# dcf77_clock.net
KiCad netlist of a schematic drawn in EAGLE
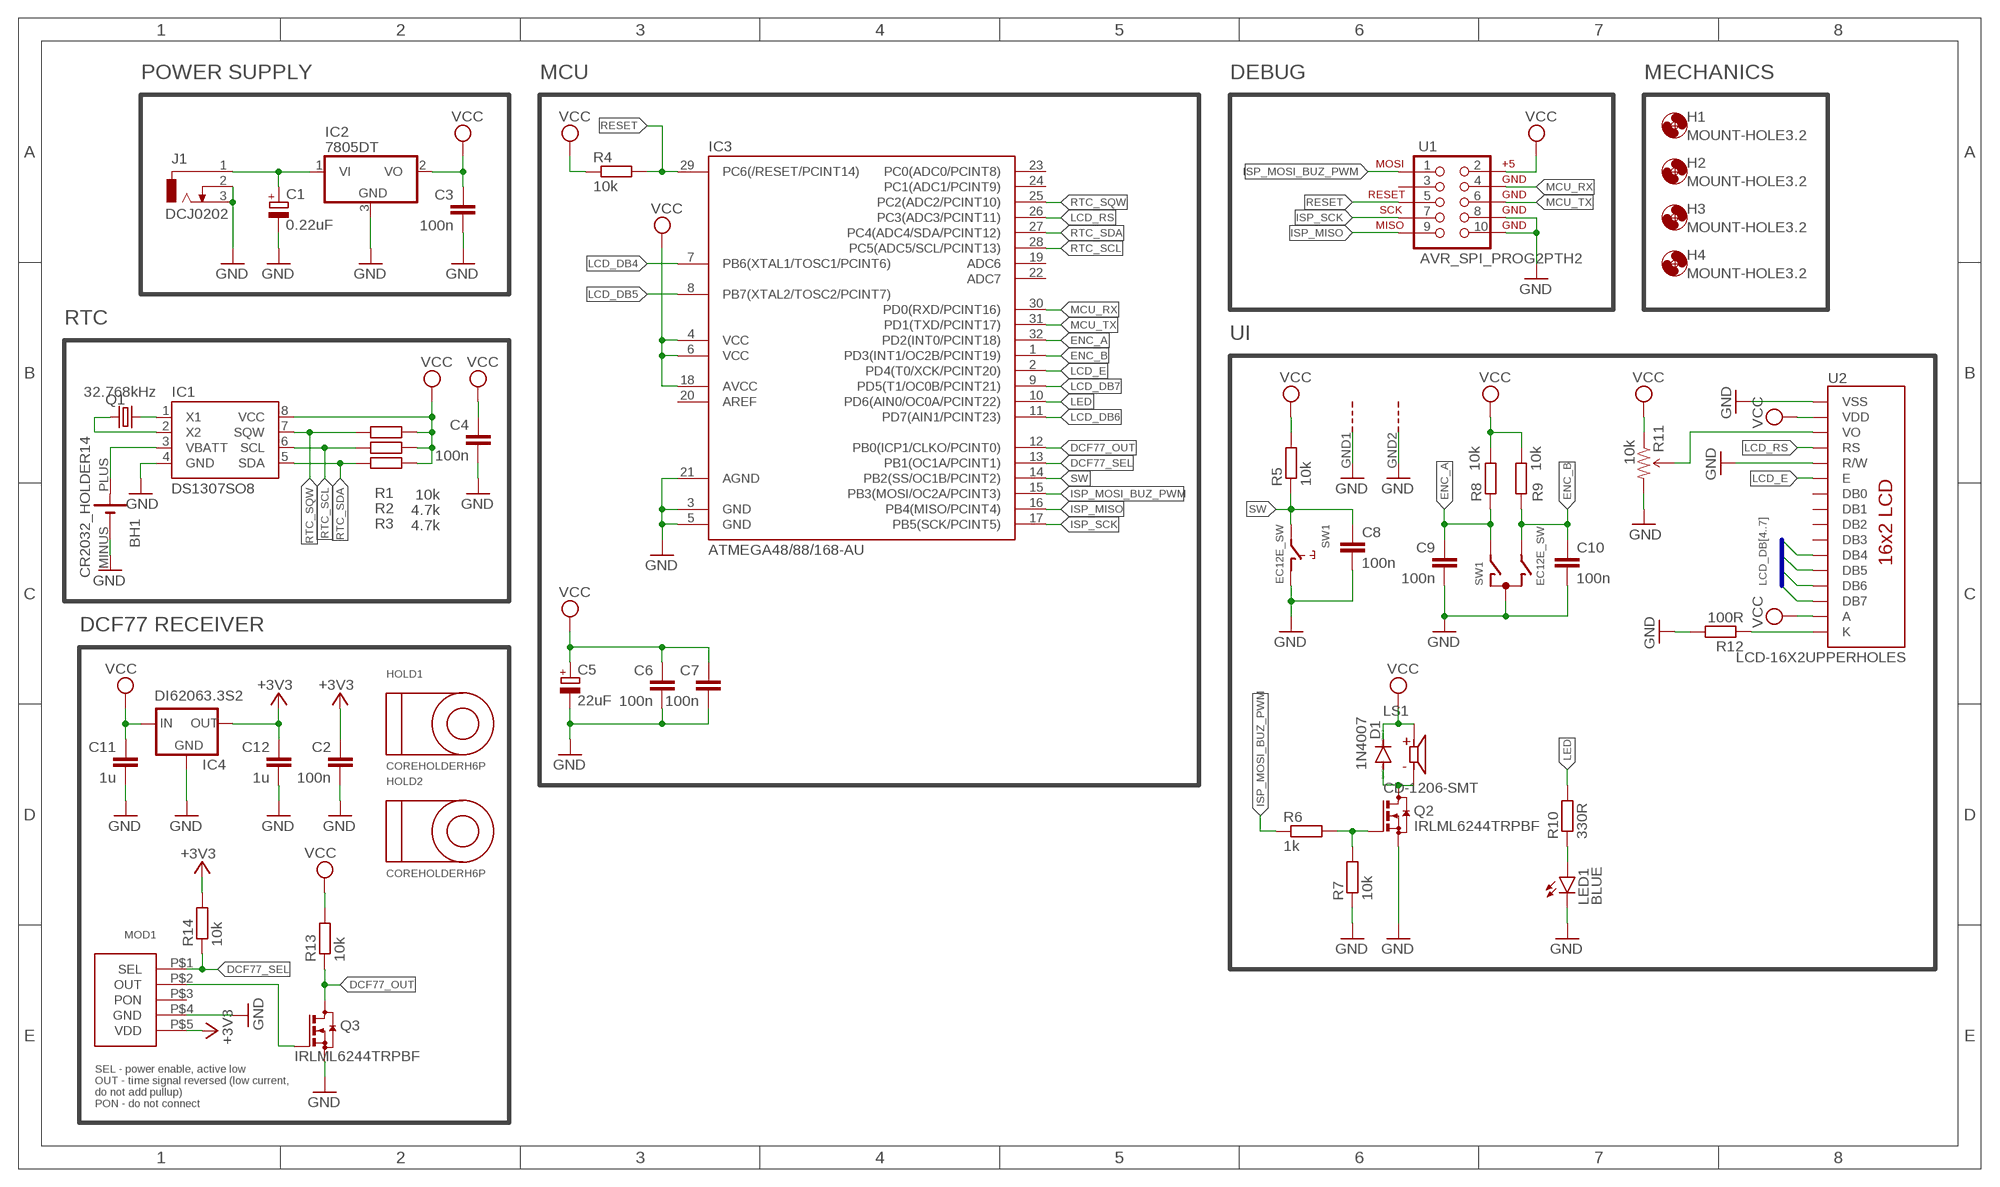
[diagram p0: schematic, sheet 1]

(export (version "E")
  (design (tool "Eeschema 10.0.6"))
  (components
    (comp (ref "BH1")
      (value "CR2032_HOLDER14")
      (footprint "eagle-import:CONNFLY-DS1092-14-B6P")
      (libsource (lib "eagle-import") (part "CR2032_HOLDER14"))
    )
    (comp (ref "C1")
      (value "0.22uF")
      (footprint "eagle-import:SMC_Z")
      (libsource (lib "eagle-import") (part "CPOL-EUSMCZ"))
    )
    (comp (ref "C2")
      (value "100n")
      (footprint "eagle-import:C0805K")
      (libsource (lib "eagle-import") (part "C-EUC0805K"))
    )
    (comp (ref "C3")
      (value "100n")
      (footprint "eagle-import:C0805K")
      (libsource (lib "eagle-import") (part "C-EUC0805K"))
    )
    (comp (ref "C4")
      (value "100n")
      (footprint "eagle-import:C0805K")
      (libsource (lib "eagle-import") (part "C-EUC0805K"))
    )
    (comp (ref "C5")
      (value "22uF")
      (footprint "eagle-import:UD-4X5,8_NICHICON")
      (libsource (lib "eagle-import") (part "CPOL-EUUD-4X5,8"))
    )
    (comp (ref "C6")
      (value "100n")
      (footprint "eagle-import:C0805K")
      (libsource (lib "eagle-import") (part "C-EUC0805K"))
    )
    (comp (ref "C7")
      (value "100n")
      (footprint "eagle-import:C0805K")
      (libsource (lib "eagle-import") (part "C-EUC0805K"))
    )
    (comp (ref "C8")
      (value "100n")
      (footprint "eagle-import:C0805K")
      (libsource (lib "eagle-import") (part "C-EUC0805K"))
    )
    (comp (ref "C9")
      (value "100n")
      (footprint "eagle-import:C0805K")
      (libsource (lib "eagle-import") (part "C-EUC0805K"))
    )
    (comp (ref "C10")
      (value "100n")
      (footprint "eagle-import:C0805K")
      (libsource (lib "eagle-import") (part "C-EUC0805K"))
    )
    (comp (ref "C11")
      (value "1u")
      (footprint "eagle-import:C0805K")
      (libsource (lib "eagle-import") (part "C-EUC0805K"))
    )
    (comp (ref "C12")
      (value "1u")
      (footprint "eagle-import:C0805K")
      (libsource (lib "eagle-import") (part "C-EUC0805K"))
    )
    (comp (ref "D1")
      (value "1N4007")
      (footprint "eagle-import:SOD123")
      (libsource (lib "eagle-import") (part "DIODE-SOD123"))
    )
    (comp (ref "H1")
      (value "MOUNT-HOLE3.2")
      (footprint "eagle-import:3,2")
      (libsource (lib "eagle-import") (part "MOUNT-HOLE3.2"))
    )
    (comp (ref "H2")
      (value "MOUNT-HOLE3.2")
      (footprint "eagle-import:3,2")
      (libsource (lib "eagle-import") (part "MOUNT-HOLE3.2"))
    )
    (comp (ref "H3")
      (value "MOUNT-HOLE3.2")
      (footprint "eagle-import:3,2")
      (libsource (lib "eagle-import") (part "MOUNT-HOLE3.2"))
    )
    (comp (ref "H4")
      (value "MOUNT-HOLE3.2")
      (footprint "eagle-import:3,2")
      (libsource (lib "eagle-import") (part "MOUNT-HOLE3.2"))
    )
    (comp (ref "HOLD1")
      (value "COREHOLDERH6P")
      (footprint "eagle-import:H6P")
      (libsource (lib "eagle-import") (part "COREHOLDERH6P"))
    )
    (comp (ref "HOLD2")
      (value "COREHOLDERH6P")
      (footprint "eagle-import:H6P")
      (libsource (lib "eagle-import") (part "COREHOLDERH6P"))
    )
    (comp (ref "IC1")
      (value "DS1307SO8")
      (footprint "eagle-import:SO08")
      (libsource (lib "eagle-import") (part "DS1307SO8"))
    )
    (comp (ref "IC2")
      (value "7805DT")
      (footprint "eagle-import:TO252")
      (libsource (lib "eagle-import") (part "78DT05"))
    )
    (comp (ref "IC3")
      (value "ATMEGA48/88/168-AU")
      (footprint "eagle-import:TQFP32-08")
      (libsource (lib "eagle-import") (part "ATMEGA48/88/168-AU"))
    )
    (comp (ref "IC4")
      (value "DI62063.3S2")
      (footprint "eagle-import:SOT23")
      (libsource (lib "eagle-import") (part "DI62063.3S2"))
    )
    (comp (ref "J1")
      (value "DCJ0202")
      (footprint "eagle-import:DCJ0202")
      (libsource (lib "eagle-import") (part "DCJ0202"))
    )
    (comp (ref "LED1")
      (value "BLUE")
      (footprint "eagle-import:CHIP-LED0805")
      (libsource (lib "eagle-import") (part "LEDCHIP-LED0805"))
    )
    (comp (ref "LS1")
      (value "CD-1206-SMT")
      (footprint "eagle-import:CUI_CD-1206-SMT")
      (fields (field (name "MF") "CUI Inc.") (field (name "MP") "CD-1206-SMT-TR"))
      (libsource (lib "eagle-import") (part "CD-1206-SMT"))
    )
    (comp (ref "MOD1")
      (value "DCF77MODULE")
      (footprint "eagle-import:DCF77MOD")
      (libsource (lib "eagle-import") (part "DCF77MODULE"))
    )
    (comp (ref "Q1")
      (value "32.768kHz")
      (footprint "eagle-import:MM20SS")
      (libsource (lib "eagle-import") (part "CRYSTALMM20SS"))
    )
    (comp (ref "Q2")
      (value "IRLML6244TRPBF")
      (footprint "eagle-import:SOT23")
      (libsource (lib "eagle-import") (part "IRLML6244TRPBF"))
    )
    (comp (ref "Q3")
      (value "IRLML6244TRPBF")
      (footprint "eagle-import:SOT23")
      (libsource (lib "eagle-import") (part "IRLML6244TRPBF"))
    )
    (comp (ref "R1")
      (value "10k")
      (footprint "eagle-import:M0805")
      (libsource (lib "eagle-import") (part "R-EU_M0805"))
    )
    (comp (ref "R2")
      (value "4.7k")
      (footprint "eagle-import:M0805")
      (libsource (lib "eagle-import") (part "R-EU_M0805"))
    )
    (comp (ref "R3")
      (value "4.7k")
      (footprint "eagle-import:M0805")
      (libsource (lib "eagle-import") (part "R-EU_M0805"))
    )
    (comp (ref "R4")
      (value "10k")
      (footprint "eagle-import:M0805")
      (libsource (lib "eagle-import") (part "R-EU_M0805"))
    )
    (comp (ref "R5")
      (value "10k")
      (footprint "eagle-import:M0805")
      (libsource (lib "eagle-import") (part "R-EU_M0805"))
    )
    (comp (ref "R6")
      (value "1k")
      (footprint "eagle-import:M0805")
      (libsource (lib "eagle-import") (part "R-EU_M0805"))
    )
    (comp (ref "R7")
      (value "10k")
      (footprint "eagle-import:M0805")
      (libsource (lib "eagle-import") (part "R-EU_M0805"))
    )
    (comp (ref "R8")
      (value "10k")
      (footprint "eagle-import:M0805")
      (libsource (lib "eagle-import") (part "R-EU_M0805"))
    )
    (comp (ref "R9")
      (value "10k")
      (footprint "eagle-import:M0805")
      (libsource (lib "eagle-import") (part "R-EU_M0805"))
    )
    (comp (ref "R10")
      (value "330R")
      (footprint "eagle-import:M0805")
      (libsource (lib "eagle-import") (part "R-EU_M0805"))
    )
    (comp (ref "R11")
      (value "10k")
      (footprint "eagle-import:TRIM_POT_PTH")
      (libsource (lib "eagle-import") (part "TRIMPOTPTH"))
    )
    (comp (ref "R12")
      (value "100R")
      (footprint "eagle-import:M0805")
      (libsource (lib "eagle-import") (part "R-EU_M0805"))
    )
    (comp (ref "R13")
      (value "10k")
      (footprint "eagle-import:M0805")
      (libsource (lib "eagle-import") (part "R-EU_M0805"))
    )
    (comp (ref "R14")
      (value "10k")
      (footprint "eagle-import:M0805")
      (libsource (lib "eagle-import") (part "R-EU_M0805"))
    )
    (comp (ref "SW1")
      (value "EC12E_SW")
      (footprint "eagle-import:ALPS_EC12E_SW")
      (fields (field (name "MPN") "EC12E2424407"))
      (libsource (lib "eagle-import") (part "EC12E_SW"))
    )
    (comp (ref "U1")
      (value "AVR_SPI_PROG2PTH2")
      (footprint "eagle-import:2X5-SHROUDED")
      (libsource (lib "eagle-import") (part "AVR_SPI_PROG2PTH2"))
    )
    (comp (ref "U2")
      (value "LCD-16X2UPPERHOLES")
      (footprint "eagle-import:LCD-16X2_UPPER_HOLES")
      (libsource (lib "eagle-import") (part "LCD-16X2UPPERHOLES"))
    )
  )
  (nets
    (net (code "1") (name "+3V3") (class "Default")
      (node (ref "C12") (pin "1") (pinfunction "1_1") (pintype "passive"))
      (node (ref "C2") (pin "1") (pinfunction "1_1") (pintype "passive"))
      (node (ref "IC4") (pin "2") (pinfunction "OUT_2") (pintype "passive"))
      (node (ref "MOD1") (pin "P$5") (pinfunction "VDD_P$5") (pintype "bidirectional"))
      (node (ref "R14") (pin "2") (pinfunction "2_2") (pintype "passive"))
    )
    (net (code "3") (name "DCF77_OUT") (class "Default")
      (node (ref "IC3") (pin "12") (pinfunction "PB0(ICP1/CLKO/PCINT0)_12") (pintype "bidirectional"))
      (node (ref "Q3") (pin "3") (pinfunction "D_3") (pintype "passive"))
      (node (ref "R13") (pin "1") (pinfunction "1_1") (pintype "passive"))
    )
    (net (code "4") (name "DCF77_SEL") (class "Default")
      (node (ref "IC3") (pin "13") (pinfunction "PB1(OC1A/PCINT1)_13") (pintype "bidirectional"))
      (node (ref "MOD1") (pin "P$1") (pinfunction "SEL_P$1") (pintype "bidirectional"))
      (node (ref "R14") (pin "1") (pinfunction "1_1") (pintype "passive"))
    )
    (net (code "5") (name "ENC_A") (class "Default")
      (node (ref "C9") (pin "1") (pinfunction "1_1") (pintype "passive"))
      (node (ref "IC3") (pin "32") (pinfunction "PD2(INT0/PCINT18)_32") (pintype "bidirectional"))
      (node (ref "R8") (pin "1") (pinfunction "1_1") (pintype "passive"))
      (node (ref "SW1") (pin "A") (pinfunction "A_A") (pintype "passive"))
    )
    (net (code "6") (name "ENC_B") (class "Default")
      (node (ref "C10") (pin "1") (pinfunction "1_1") (pintype "passive"))
      (node (ref "IC3") (pin "1") (pinfunction "PD3(INT1/OC2B/PCINT19)_1") (pintype "bidirectional"))
      (node (ref "R9") (pin "1") (pinfunction "1_1") (pintype "passive"))
      (node (ref "SW1") (pin "B") (pinfunction "B_B") (pintype "passive"))
    )
    (net (code "7") (name "GND") (class "Default")
      (node (ref "BH1") (pin "MINUS") (pinfunction "MINUS_MINUS") (pintype "passive"))
      (node (ref "C1") (pin "-") (pinfunction "-_-") (pintype "passive"))
      (node (ref "C10") (pin "2") (pinfunction "2_2") (pintype "passive"))
      (node (ref "C11") (pin "2") (pinfunction "2_2") (pintype "passive"))
      (node (ref "C12") (pin "2") (pinfunction "2_2") (pintype "passive"))
      (node (ref "C2") (pin "2") (pinfunction "2_2") (pintype "passive"))
      (node (ref "C3") (pin "2") (pinfunction "2_2") (pintype "passive"))
      (node (ref "C4") (pin "2") (pinfunction "2_2") (pintype "passive"))
      (node (ref "C5") (pin "-") (pinfunction "-_-") (pintype "passive"))
      (node (ref "C6") (pin "2") (pinfunction "2_2") (pintype "passive"))
      (node (ref "C7") (pin "2") (pinfunction "2_2") (pintype "passive"))
      (node (ref "C8") (pin "2") (pinfunction "2_2") (pintype "passive"))
      (node (ref "C9") (pin "2") (pinfunction "2_2") (pintype "passive"))
      (node (ref "IC1") (pin "4") (pinfunction "GND_4") (pintype "bidirectional"))
      (node (ref "IC2") (pin "3") (pinfunction "GND_3") (pintype "passive"))
      (node (ref "IC3") (pin "21") (pinfunction "AGND_21") (pintype "power_in"))
      (node (ref "IC3") (pin "3") (pinfunction "GND_3") (pintype "power_in"))
      (node (ref "IC3") (pin "5") (pinfunction "GND_5") (pintype "power_in"))
      (node (ref "IC4") (pin "1") (pinfunction "GND_1") (pintype "input"))
      (node (ref "J1") (pin "2") (pinfunction "2_2") (pintype "passive"))
      (node (ref "J1") (pin "3") (pinfunction "3_3") (pintype "passive"))
      (node (ref "LED1") (pin "C") (pinfunction "C_C") (pintype "passive"))
      (node (ref "MOD1") (pin "P$4") (pinfunction "GND_P$4") (pintype "bidirectional"))
      (node (ref "Q2") (pin "2") (pinfunction "S_2") (pintype "passive"))
      (node (ref "Q3") (pin "2") (pinfunction "S_2") (pintype "passive"))
      (node (ref "R11") (pin "3") (pinfunction "CW_3") (pintype "passive"))
      (node (ref "R12") (pin "2") (pinfunction "2_2") (pintype "passive"))
      (node (ref "R7") (pin "1") (pinfunction "1_1") (pintype "passive"))
      (node (ref "SW1") (pin "C") (pinfunction "C_C") (pintype "passive"))
      (node (ref "SW1") (pin "D") (pinfunction "1_D") (pintype "passive"))
      (node (ref "SW1") (pin "GND1") (pinfunction "G_GND1") (pintype "passive"))
      (node (ref "SW1") (pin "GND2") (pinfunction "G_GND2") (pintype "passive"))
      (node (ref "U1") (pin "10") (pinfunction "10_10") (pintype "passive"))
      (node (ref "U1") (pin "8") (pinfunction "8_8") (pintype "passive"))
      (node (ref "U2") (pin "1") (pinfunction "VSS_1") (pintype "power_in"))
      (node (ref "U2") (pin "5") (pinfunction "R/W_5") (pintype "input"))
    )
    (net (code "8") (name "ISP_MISO") (class "Default")
      (node (ref "IC3") (pin "16") (pinfunction "PB4(MISO/PCINT4)_16") (pintype "bidirectional"))
      (node (ref "U1") (pin "9") (pinfunction "9_9") (pintype "passive"))
    )
    (net (code "9") (name "ISP_MOSI_BUZ_PWM") (class "Default")
      (node (ref "IC3") (pin "15") (pinfunction "PB3(MOSI/OC2A/PCINT3)_15") (pintype "bidirectional"))
      (node (ref "R6") (pin "1") (pinfunction "1_1") (pintype "passive"))
      (node (ref "U1") (pin "1") (pinfunction "1_1") (pintype "passive"))
    )
    (net (code "10") (name "ISP_SCK") (class "Default")
      (node (ref "IC3") (pin "17") (pinfunction "PB5(SCK/PCINT5)_17") (pintype "bidirectional"))
      (node (ref "U1") (pin "7") (pinfunction "7_7") (pintype "passive"))
    )
    (net (code "11") (name "LCD_DB4") (class "Default")
      (node (ref "IC3") (pin "7") (pinfunction "PB6(XTAL1/TOSC1/PCINT6)_7") (pintype "bidirectional"))
      (node (ref "U2") (pin "11") (pinfunction "DB4_11") (pintype "bidirectional"))
    )
    (net (code "12") (name "LCD_DB5") (class "Default")
      (node (ref "IC3") (pin "8") (pinfunction "PB7(XTAL2/TOSC2/PCINT7)_8") (pintype "bidirectional"))
      (node (ref "U2") (pin "12") (pinfunction "DB5_12") (pintype "bidirectional"))
    )
    (net (code "13") (name "LCD_DB6") (class "Default")
      (node (ref "IC3") (pin "11") (pinfunction "PD7(AIN1/PCINT23)_11") (pintype "bidirectional"))
      (node (ref "U2") (pin "13") (pinfunction "DB6_13") (pintype "bidirectional"))
    )
    (net (code "14") (name "LCD_DB7") (class "Default")
      (node (ref "IC3") (pin "9") (pinfunction "PD5(T1/OC0B/PCINT21)_9") (pintype "bidirectional"))
      (node (ref "U2") (pin "14") (pinfunction "DB7_14") (pintype "bidirectional"))
    )
    (net (code "15") (name "LCD_E") (class "Default")
      (node (ref "IC3") (pin "2") (pinfunction "PD4(T0/XCK/PCINT20)_2") (pintype "bidirectional"))
      (node (ref "U2") (pin "6") (pinfunction "E_6") (pintype "input"))
    )
    (net (code "16") (name "LCD_RS") (class "Default")
      (node (ref "IC3") (pin "26") (pinfunction "PC3(ADC3/PCINT11)_26") (pintype "bidirectional"))
      (node (ref "U2") (pin "4") (pinfunction "RS_4") (pintype "input"))
    )
    (net (code "17") (name "LED") (class "Default")
      (node (ref "IC3") (pin "10") (pinfunction "PD6(AIN0/OC0A/PCINT22)_10") (pintype "bidirectional"))
      (node (ref "R10") (pin "2") (pinfunction "2_2") (pintype "passive"))
    )
    (net (code "18") (name "MCU_RX") (class "Default")
      (node (ref "IC3") (pin "30") (pinfunction "PD0(RXD/PCINT16)_30") (pintype "bidirectional"))
      (node (ref "U1") (pin "4") (pinfunction "4_4") (pintype "passive"))
    )
    (net (code "19") (name "MCU_TX") (class "Default")
      (node (ref "IC3") (pin "31") (pinfunction "PD1(TXD/PCINT17)_31") (pintype "bidirectional"))
      (node (ref "U1") (pin "6") (pinfunction "6_6") (pintype "passive"))
    )
    (net (code "20") (name "Net-(IC1-VBATT)") (class "Default")
      (node (ref "BH1") (pin "PLUS") (pinfunction "PLUS_PLUS") (pintype "passive"))
      (node (ref "IC1") (pin "3") (pinfunction "VBATT_3") (pintype "bidirectional"))
    )
    (net (code "21") (name "Net-(IC1-X1)") (class "Default")
      (node (ref "IC1") (pin "1") (pinfunction "X1_1") (pintype "bidirectional"))
      (node (ref "Q1") (pin "1") (pinfunction "1_1") (pintype "passive"))
    )
    (net (code "22") (name "Net-(IC1-X2)") (class "Default")
      (node (ref "IC1") (pin "2") (pinfunction "X2_2") (pintype "bidirectional"))
      (node (ref "Q1") (pin "4") (pinfunction "2_4") (pintype "passive"))
    )
    (net (code "23") (name "Net-(IC2-VI)") (class "Default")
      (node (ref "C1") (pin "+") (pinfunction "+_+") (pintype "passive"))
      (node (ref "IC2") (pin "1") (pinfunction "VI_1") (pintype "input"))
      (node (ref "J1") (pin "1") (pinfunction "1_1") (pintype "passive"))
    )
    (net (code "24") (name "Net-(LED1-PadA)") (class "Default")
      (node (ref "LED1") (pin "A") (pinfunction "A_A") (pintype "passive"))
      (node (ref "R10") (pin "1") (pinfunction "1_1") (pintype "passive"))
    )
    (net (code "25") (name "Net-(MOD1-OUT)") (class "Default")
      (node (ref "MOD1") (pin "P$2") (pinfunction "OUT_P$2") (pintype "bidirectional"))
      (node (ref "Q3") (pin "1") (pinfunction "G_1") (pintype "passive"))
    )
    (net (code "26") (name "Net-(Q2-D)") (class "Default")
      (node (ref "D1") (pin "A") (pinfunction "A_A") (pintype "passive"))
      (node (ref "LS1") (pin "M") (pinfunction "M_M") (pintype "passive"))
      (node (ref "Q2") (pin "3") (pinfunction "D_3") (pintype "passive"))
    )
    (net (code "27") (name "Net-(Q2-G)") (class "Default")
      (node (ref "Q2") (pin "1") (pinfunction "G_1") (pintype "passive"))
      (node (ref "R6") (pin "2") (pinfunction "2_2") (pintype "passive"))
      (node (ref "R7") (pin "2") (pinfunction "2_2") (pintype "passive"))
    )
    (net (code "28") (name "Net-(R11-WIPER)") (class "Default")
      (node (ref "R11") (pin "2") (pinfunction "WIPER_2") (pintype "passive"))
      (node (ref "U2") (pin "3") (pinfunction "VO_3") (pintype "bidirectional"))
    )
    (net (code "29") (name "Net-(U2-K)") (class "Default")
      (node (ref "R12") (pin "1") (pinfunction "1_1") (pintype "passive"))
      (node (ref "U2") (pin "16") (pinfunction "K_16") (pintype "power_in"))
    )
    (net (code "30") (name "RESET") (class "Default")
      (node (ref "IC3") (pin "29") (pinfunction "PC6(/RESET/PCINT14)_29") (pintype "bidirectional"))
      (node (ref "R4") (pin "2") (pinfunction "2_2") (pintype "passive"))
      (node (ref "U1") (pin "5") (pinfunction "5_5") (pintype "passive"))
    )
    (net (code "31") (name "RTC_SCL") (class "Default")
      (node (ref "IC1") (pin "6") (pinfunction "SCL_6") (pintype "bidirectional"))
      (node (ref "IC3") (pin "28") (pinfunction "PC5(ADC5/SCL/PCINT13)_28") (pintype "bidirectional"))
      (node (ref "R2") (pin "2") (pinfunction "2_2") (pintype "passive"))
    )
    (net (code "32") (name "RTC_SDA") (class "Default")
      (node (ref "IC1") (pin "5") (pinfunction "SDA_5") (pintype "bidirectional"))
      (node (ref "IC3") (pin "27") (pinfunction "PC4(ADC4/SDA/PCINT12)_27") (pintype "bidirectional"))
      (node (ref "R3") (pin "2") (pinfunction "2_2") (pintype "passive"))
    )
    (net (code "33") (name "RTC_SQW") (class "Default")
      (node (ref "IC1") (pin "7") (pinfunction "SQW_7") (pintype "bidirectional"))
      (node (ref "IC3") (pin "25") (pinfunction "PC2(ADC2/PCINT10)_25") (pintype "bidirectional"))
      (node (ref "R1") (pin "2") (pinfunction "2_2") (pintype "passive"))
    )
    (net (code "34") (name "SW") (class "Default")
      (node (ref "C8") (pin "1") (pinfunction "1_1") (pintype "passive"))
      (node (ref "IC3") (pin "14") (pinfunction "PB2(SS/OC1B/PCINT2)_14") (pintype "bidirectional"))
      (node (ref "R5") (pin "1") (pinfunction "1_1") (pintype "passive"))
      (node (ref "SW1") (pin "E") (pinfunction "2_E") (pintype "passive"))
    )
    (net (code "35") (name "VCC") (class "Default")
      (node (ref "C11") (pin "1") (pinfunction "1_1") (pintype "passive"))
      (node (ref "C3") (pin "1") (pinfunction "1_1") (pintype "passive"))
      (node (ref "C4") (pin "1") (pinfunction "1_1") (pintype "passive"))
      (node (ref "C5") (pin "+") (pinfunction "+_+") (pintype "passive"))
      (node (ref "C6") (pin "1") (pinfunction "1_1") (pintype "passive"))
      (node (ref "C7") (pin "1") (pinfunction "1_1") (pintype "passive"))
      (node (ref "D1") (pin "C") (pinfunction "C_C") (pintype "passive"))
      (node (ref "IC1") (pin "8") (pinfunction "VCC_8") (pintype "bidirectional"))
      (node (ref "IC2") (pin "2") (pinfunction "VO_2") (pintype "passive"))
      (node (ref "IC3") (pin "18") (pinfunction "AVCC_18") (pintype "passive"))
      (node (ref "IC3") (pin "4") (pinfunction "VCC_4") (pintype "power_in"))
      (node (ref "IC3") (pin "6") (pinfunction "VCC_6") (pintype "power_in"))
      (node (ref "IC4") (pin "3") (pinfunction "IN_3") (pintype "input"))
      (node (ref "LS1") (pin "P") (pinfunction "P_P") (pintype "passive"))
      (node (ref "R1") (pin "1") (pinfunction "1_1") (pintype "passive"))
      (node (ref "R11") (pin "1") (pinfunction "CCW_1") (pintype "passive"))
      (node (ref "R13") (pin "2") (pinfunction "2_2") (pintype "passive"))
      (node (ref "R2") (pin "1") (pinfunction "1_1") (pintype "passive"))
      (node (ref "R3") (pin "1") (pinfunction "1_1") (pintype "passive"))
      (node (ref "R4") (pin "1") (pinfunction "1_1") (pintype "passive"))
      (node (ref "R5") (pin "2") (pinfunction "2_2") (pintype "passive"))
      (node (ref "R8") (pin "2") (pinfunction "2_2") (pintype "passive"))
      (node (ref "R9") (pin "2") (pinfunction "2_2") (pintype "passive"))
      (node (ref "U1") (pin "2") (pinfunction "2_2") (pintype "passive"))
      (node (ref "U2") (pin "15") (pinfunction "A_15") (pintype "power_in"))
      (node (ref "U2") (pin "2") (pinfunction "VDD_2") (pintype "power_in"))
    )
    (net (code "36") (name "unconnected-(IC3-ADC6-Pad19)") (class "Default")
      (node (ref "IC3") (pin "19") (pinfunction "ADC6_19") (pintype "passive"))
    )
    (net (code "37") (name "unconnected-(IC3-ADC7-Pad22)") (class "Default")
      (node (ref "IC3") (pin "22") (pinfunction "ADC7_22") (pintype "passive"))
    )
    (net (code "38") (name "unconnected-(IC3-AREF-Pad20)") (class "Default")
      (node (ref "IC3") (pin "20") (pinfunction "AREF_20") (pintype "passive"))
    )
    (net (code "39") (name "unconnected-(IC3-PC0(ADC0{slash}PCINT8)-Pad23)") (class "Default")
      (node (ref "IC3") (pin "23") (pinfunction "PC0(ADC0/PCINT8)_23") (pintype "bidirectional"))
    )
    (net (code "40") (name "unconnected-(IC3-PC1(ADC1{slash}PCINT9)-Pad24)") (class "Default")
      (node (ref "IC3") (pin "24") (pinfunction "PC1(ADC1/PCINT9)_24") (pintype "bidirectional"))
    )
    (net (code "41") (name "unconnected-(MOD1-PON-PadP$3)") (class "Default")
      (node (ref "MOD1") (pin "P$3") (pinfunction "PON_P$3") (pintype "bidirectional"))
    )
    (net (code "42") (name "unconnected-(U1-Pad3)") (class "Default")
      (node (ref "U1") (pin "3") (pinfunction "3_3") (pintype "passive"))
    )
    (net (code "43") (name "unconnected-(U2-DB0-Pad7)") (class "Default")
      (node (ref "U2") (pin "7") (pinfunction "DB0_7") (pintype "bidirectional"))
    )
    (net (code "44") (name "unconnected-(U2-DB1-Pad8)") (class "Default")
      (node (ref "U2") (pin "8") (pinfunction "DB1_8") (pintype "bidirectional"))
    )
    (net (code "45") (name "unconnected-(U2-DB2-Pad9)") (class "Default")
      (node (ref "U2") (pin "9") (pinfunction "DB2_9") (pintype "bidirectional"))
    )
    (net (code "46") (name "unconnected-(U2-DB3-Pad10)") (class "Default")
      (node (ref "U2") (pin "10") (pinfunction "DB3_10") (pintype "bidirectional"))
    )
  )
)
